# power.net
KiCad netlist of a schematic drawn in Altium Designer
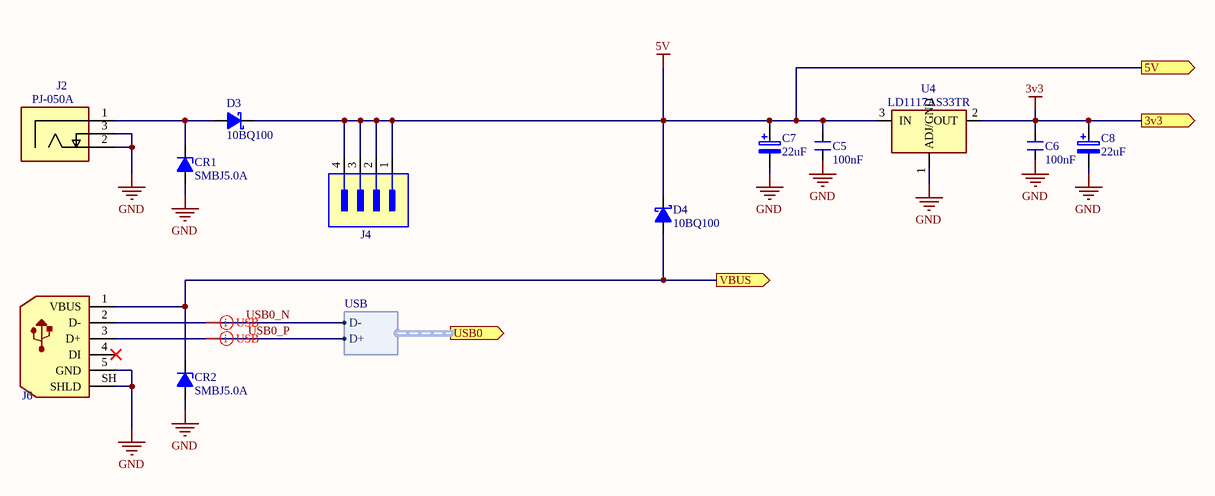
[diagram p0: power.SchDoc]

(export (version "E")
  (design (tool "Eeschema 10.0.6"))
  (components
    (comp (ref "C5")
      (value "100nF")
      (footprint "CAP0603")
      (description "Tolerance ±10%\nRated Voltage 50Vdc\nTemperature 0±30ppm/℃")
      (fields (field (name "PART NUMBER") "GCM188R71H104KA57J") (field (name "TOLERANCE") "10%"))
      (libsource (lib "Lib_Kam") (part "Capacitor"))
    )
    (comp (ref "C6")
      (value "100nF")
      (footprint "CAP0603")
      (description "Tolerance ±10%\nRated Voltage 50Vdc\nTemperature 0±30ppm/℃")
      (fields (field (name "PART NUMBER") "GCM188R71H104KA57J") (field (name "TOLERANCE") "10%"))
      (libsource (lib "Lib_Kam") (part "Capacitor"))
    )
    (comp (ref "C7")
      (value "22uF")
      (footprint "CAP TANT B")
      (fields
        (field (name "PART NUMBER") "TAJB226K016RNJ")
        (field (name "TOLERANCE") "10%")
        (field (name "MANUFACTURER") "KYOCERA AVX")
      )
      (libsource (lib "Lib_Kam") (part "Capacitor_polar_tantalum"))
    )
    (comp (ref "C8")
      (value "22uF")
      (footprint "CAP TANT B")
      (fields
        (field (name "PART NUMBER") "TAJB226K016RNJ")
        (field (name "TOLERANCE") "10%")
        (field (name "MANUFACTURER") "KYOCERA AVX")
      )
      (libsource (lib "Lib_Kam") (part "Capacitor_polar_tantalum"))
    )
    (comp (ref "CR1")
      (value "SMBJ5.0A")
      (footprint "DO-214AA-2_SMB")
      (description "ESD Suppressors / TVS Diodes 600W 5V Unidirect")
      (fields (field (name "MANUFACTURER") "Bourns"))
      (libsource (lib "Lib_Kam") (part "TVS_Diode"))
    )
    (comp (ref "CR2")
      (value "SMBJ5.0A")
      (footprint "DO-214AA-2_SMB")
      (description "ESD Suppressors / TVS Diodes 600W 5V Unidirect")
      (fields (field (name "MANUFACTURER") "Bourns"))
      (libsource (lib "Lib_Kam") (part "TVS_Diode"))
    )
    (comp (ref "D3")
      (value "10BQ100")
      (footprint "DO-214AA-2_SMB")
      (description "Schottky Diodes & Rectifiers 1A 100V Single Die Schottky Rectifier")
      (fields (field (name "MANUFACTURER") "Hottech"))
      (libsource (lib "Lib_Kam") (part "Diode_Schottky"))
    )
    (comp (ref "D4")
      (value "10BQ100")
      (footprint "DO-214AA-2_SMB")
      (description "Schottky Diodes & Rectifiers 1A 100V Single Die Schottky Rectifier")
      (fields (field (name "MANUFACTURER") "Hottech"))
      (libsource (lib "Lib_Kam") (part "Diode_Schottky"))
    )
    (comp (ref "J2")
      (value "PJ-050A")
      (footprint "CUI_PJ050A")
      (description "DC Power Connectors Power Jacks Right Angle")
      (fields
        (field (name "MANUFACTURER PART NUMBER") "MJ-2506N")
        (field (name "MANUFACTURER") "CUI Devices")
      )
      (libsource (lib "Lib_Kam") (part "JACK_MONO"))
    )
    (comp (ref "J4")
      (value "PM254-2-02-Z-8.5")
      (footprint "254-2-2-Fem")
      (fields (field (name "MANUFACTURER") "HCTL"))
      (libsource (lib "Lib_Kam") (part "Header_4"))
    )
    (comp (ref "J6")
      (value "micro-USB female")
      (footprint "GCT_USB_Micro_B")
      (description "USB Connectors Micro B Skt, Bottom-SMT, R/A, 30u, No Peg, W/shell stake, No MEF,T&R")
      (fields (field (name "PART NUMBER") "640-USB3076-30-A") (field (name "MANUFACTURER") "GCT"))
      (libsource (lib "Lib_Kam") (part "USB micro"))
    )
    (comp (ref "U4")
      (value "LD1117AS33TR")
      (footprint "SOT-223")
      (description "Linear Voltage Regulators 3.3V 1A Positive")
      (fields (field (name "MANUFACTURER") "STMicroelectronics"))
      (libsource (lib "Lib_Kam") (part "LD1117A"))
    )
  )
  (nets
    (net (code "2") (name "/USB0_N") (class "Default")
      (node (ref "J6") (pin "2") (pinfunction "D-_2") (pintype "passive"))
    )
    (net (code "3") (name "/USB0_P") (class "Default")
      (node (ref "J6") (pin "3") (pinfunction "D+_3") (pintype "passive"))
    )
    (net (code "4") (name "/VBUS") (class "Default")
      (node (ref "CR2") (pin "1") (pinfunction "C_1") (pintype "passive"))
      (node (ref "D4") (pin "2") (pinfunction "A_2") (pintype "passive"))
      (node (ref "J6") (pin "1") (pinfunction "VBUS_1") (pintype "power_in"))
    )
    (net (code "6") (name "3v3") (class "Default")
      (node (ref "C6") (pin "2") (pinfunction "2_2") (pintype "passive"))
      (node (ref "C8") (pin "1") (pinfunction "1_1") (pintype "passive"))
      (node (ref "U4") (pin "2") (pinfunction "OUT_2") (pintype "passive"))
    )
    (net (code "7") (name "5V") (class "Default")
      (node (ref "C5") (pin "2") (pinfunction "2_2") (pintype "passive"))
      (node (ref "C7") (pin "1") (pinfunction "1_1") (pintype "passive"))
      (node (ref "D3") (pin "1") (pinfunction "C_1") (pintype "passive"))
      (node (ref "D4") (pin "1") (pinfunction "C_1") (pintype "passive"))
      (node (ref "J4") (pin "1") (pinfunction "1_1") (pintype "passive"))
      (node (ref "J4") (pin "2") (pinfunction "2_2") (pintype "passive"))
      (node (ref "J4") (pin "3") (pinfunction "3_3") (pintype "passive"))
      (node (ref "J4") (pin "4") (pinfunction "4_4") (pintype "passive"))
      (node (ref "U4") (pin "3") (pinfunction "IN_3") (pintype "passive"))
    )
    (net (code "8") (name "GND") (class "Default")
      (node (ref "C5") (pin "1") (pinfunction "2_1") (pintype "passive"))
      (node (ref "C6") (pin "1") (pinfunction "2_1") (pintype "passive"))
      (node (ref "C7") (pin "2") (pinfunction "2_2") (pintype "passive"))
      (node (ref "C8") (pin "2") (pinfunction "2_2") (pintype "passive"))
      (node (ref "CR1") (pin "2") (pinfunction "A_2") (pintype "passive"))
      (node (ref "CR2") (pin "2") (pinfunction "A_2") (pintype "passive"))
      (node (ref "J2") (pin "2") (pinfunction "2_2") (pintype "passive"))
      (node (ref "J2") (pin "3") (pinfunction "3_3") (pintype "passive"))
      (node (ref "J6") (pin "5") (pinfunction "GND_5") (pintype "power_in"))
      (node (ref "J6") (pin "SH") (pinfunction "SHLD_SH") (pintype "passive"))
      (node (ref "U4") (pin "1") (pinfunction "ADJ/GND_1") (pintype "passive"))
    )
    (net (code "9") (name "Net-(CR1-C)") (class "Default")
      (node (ref "CR1") (pin "1") (pinfunction "C_1") (pintype "passive"))
      (node (ref "D3") (pin "2") (pinfunction "A_2") (pintype "passive"))
      (node (ref "J2") (pin "1") (pinfunction "1_1") (pintype "passive"))
    )
    (net (code "10") (name "unconnected-(J6-DI-Pad4)") (class "Default")
      (node (ref "J6") (pin "4") (pinfunction "DI_4") (pintype "passive+no_connect"))
    )
  )
)
